# Power_Supplies.net
KiCad netlist of a schematic drawn in Altium Designer
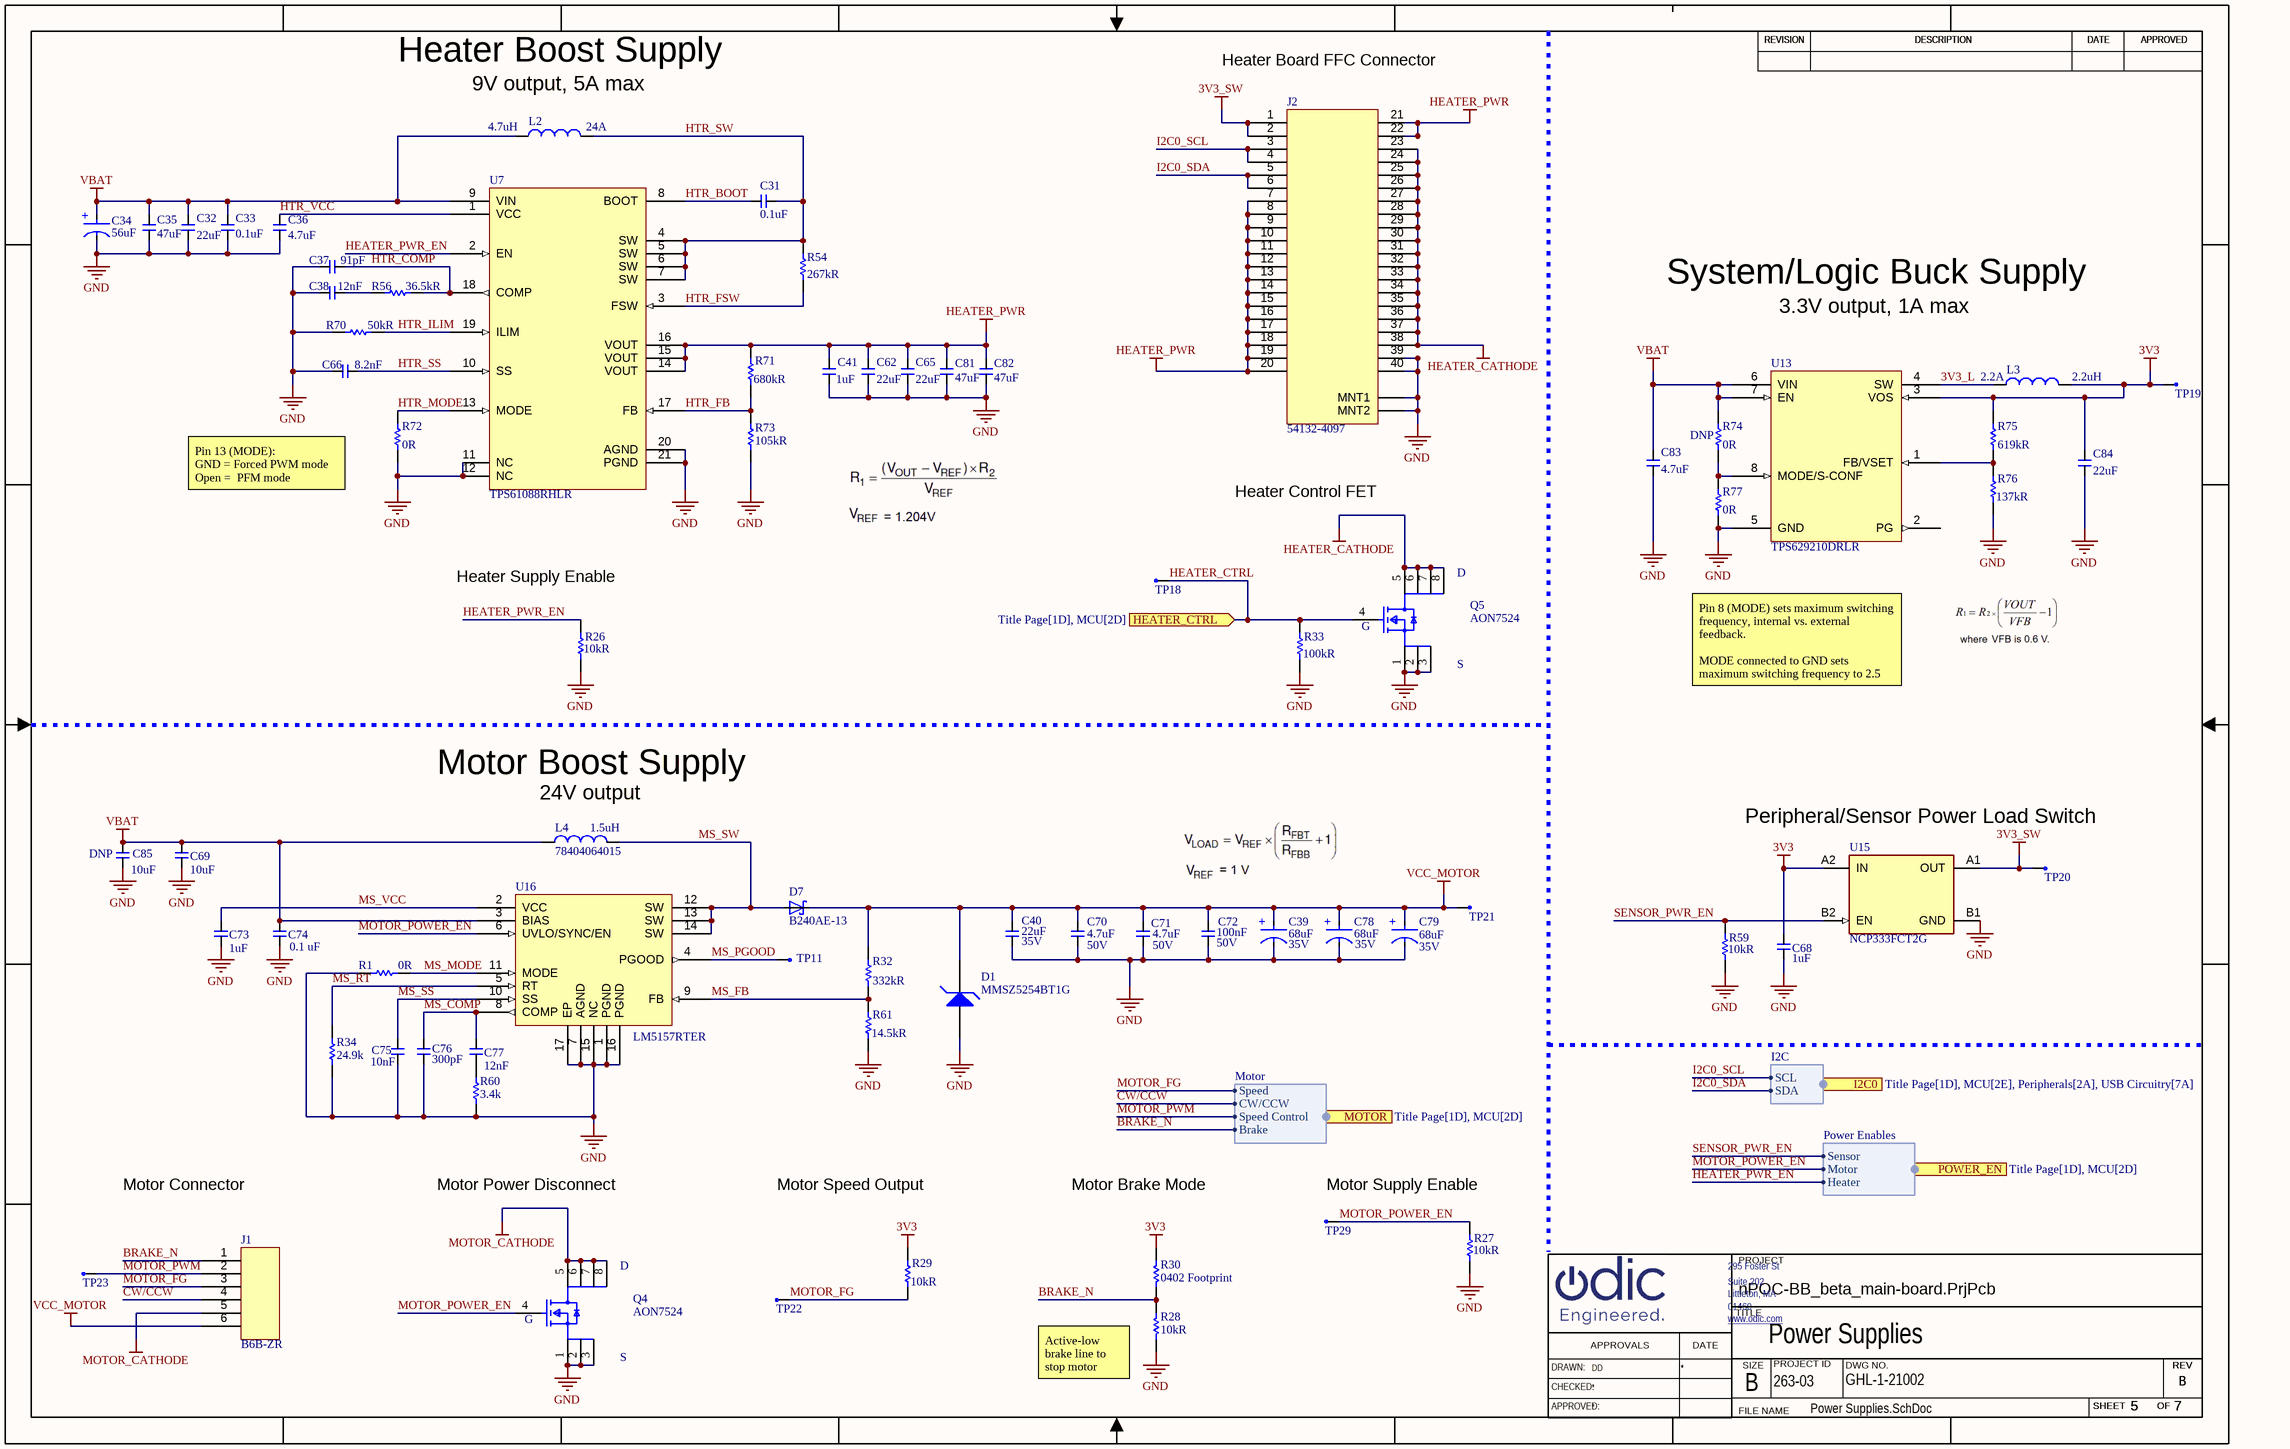
[diagram p0: Power Supplies.SchDoc]

(export (version "E")
  (design (tool "Eeschema 10.0.6"))
  (components
    (comp (ref "C31")
      (value "0.1uF")
      (footprint "C0402")
      (description "Ceramic capacitor SMD 0402 100nF 16V X7R 10%")
      (fields (field (name "VOLTAGE") "16V") (field (name "TOLERANCE") "10%"))
      (libsource (lib "Odic Inc") (part "cAP"))
    )
    (comp (ref "C32")
      (value "22uF")
      (footprint "C1206")
      (description "1206 22 uF 16 V ±10% Tolerance X5R SMT Multilayer Ceramic Capacitor")
      (fields (field (name "VOLTAGE") "16V") (field (name "TOLERANCE") "10%"))
      (libsource (lib "Odic Inc") (part "cAP"))
    )
    (comp (ref "C33")
      (value "0.1uF")
      (footprint "C0402")
      (description "Ceramic capacitor SMD 0402 100nF 16V X7R 10%")
      (fields (field (name "VOLTAGE") "16V") (field (name "TOLERANCE") "10%"))
      (libsource (lib "Odic Inc") (part "cAP"))
    )
    (comp (ref "C34")
      (value "56uF")
      (footprint "cap_panasonic_svpf_code-b6")
      (description "Cap Aluminum Polymer 56uF 20VDC 20%( 5 X 5.9mm) SMD 0.03 Ohm 2800mA 5000h 105C T/R")
      (fields (field (name "VOLTAGE") "20V") (field (name "TOLERANCE") "20%"))
      (libsource (lib "Odic Inc") (part "polcap"))
    )
    (comp (ref "C35")
      (value "47uF")
      (footprint "C1210")
      (description "Multilayer Ceramic Capacitor, 47 uF, 16 V, 10%, X5R, 1210 [3225 Metric]")
      (fields (field (name "TOLERANCE") "10%") (field (name "Comment") "C1210_47u_16V_10pct"))
      (libsource (lib "Odic Inc") (part "cAP"))
    )
    (comp (ref "C36")
      (value "4.7uF")
      (footprint "C0402")
      (description "Cap Ceramic 4.7uF 10V X5R 20% SMD 0402 85°C Paper T/R")
      (fields (field (name "TOLERANCE") "20%"))
      (libsource (lib "Odic Inc") (part "cAP"))
    )
    (comp (ref "C37")
      (value "91pF")
      (footprint "C0402")
      (description "Multilayer Ceramic Capacitors MLCC - SMD/SMT 50V 91pF C0G 0402 5%")
      (fields (field (name "TOLERANCE") "5%") (field (name "Comment") "C0402_91p_50V_5pct"))
      (libsource (lib "Odic Inc") (part "cAP"))
    )
    (comp (ref "C38")
      (value "12nF")
      (footprint "C0402")
      (description "0402 12 nF 16 V ±10% Tolerance X7R SMT Multilayer Ceramic Capacitor")
      (fields (field (name "VOLTAGE") "16V") (field (name "TOLERANCE") "10%"))
      (libsource (lib "Odic Inc") (part "cAP"))
    )
    (comp (ref "C39")
      (value "68uF")
      (footprint "C7361-38")
      (description "Cap Tant Solid 68uF 35V V CASE 20% (7.3 X 6.1 X 3.45mm) SMD 7361-38 0.5 Ohm 125AHA T/R")
      (fields
        (field (name "VOLTAGE RATING") "35V")
        (field (name "TOLERANCE") "20%")
        (field (name "Comment") "TAJV686M035RNJ")
      )
      (libsource (lib "Odic Inc") (part "polcap"))
    )
    (comp (ref "C40")
      (value "22uF")
      (footprint "c0805")
      (description "Multilayer Ceramic Capacitor, 22 uF, 35 V, ± 20%, X5R, 0805 [2012 Metric]")
      (fields
        (field (name "VOLTAGE RATING") "35V")
        (field (name "TOLERANCE") "20%")
        (field (name "Comment") "C0805_22u_35V_20pct")
      )
      (libsource (lib "Odic Inc") (part "cAP"))
    )
    (comp (ref "C41")
      (value "C0603_1u_25V_10pct")
      (footprint "C0603")
      (description "Multilayer Ceramic Capacitors (High dielectric type), 25V, 1 uF, ± 10 %, 0603, X5R/B, RoHS")
      (fields
        (field (name "CAPACITANCE") "1uF")
        (field (name "TOLERANCE") "10%")
        (field (name "VOLTAGE") "25V")
      )
      (libsource (lib "Odic Inc") (part "cAP"))
    )
    (comp (ref "C62")
      (value "22uF")
      (footprint "C1206")
      (description "1206 22 uF 16 V ±10% Tolerance X5R SMT Multilayer Ceramic Capacitor")
      (fields (field (name "VOLTAGE") "16V") (field (name "TOLERANCE") "10%"))
      (libsource (lib "Odic Inc") (part "cAP"))
    )
    (comp (ref "C65")
      (value "22uF")
      (footprint "C1206")
      (description "1206 22 uF 16 V ±10% Tolerance X5R SMT Multilayer Ceramic Capacitor")
      (fields (field (name "VOLTAGE") "16V") (field (name "TOLERANCE") "10%"))
      (libsource (lib "Odic Inc") (part "cAP"))
    )
    (comp (ref "C66")
      (value "8.2nF")
      (footprint "C0402")
      (description "0402 8.2 nF 16 V ±10% Tolerance X7R SMT Multilayer Ceramic Capacitor")
      (fields (field (name "TOLERANCE") "10%") (field (name "Comment") "C0402_8n2_16V_10pct"))
      (libsource (lib "Odic Inc") (part "cAP"))
    )
    (comp (ref "C68")
      (value "C0402_1u_6V3_10pct")
      (footprint "C0402")
      (description "Cap Ceramic 1uF 6.3V X5R 10% SMD 0402 85C Paper T/R")
      (fields (field (name "CAPACITANCE") "1uF") (field (name "TOLERANCE") "10%"))
      (libsource (lib "Odic Inc") (part "cAP"))
    )
    (comp (ref "C69")
      (value "10uF")
      (footprint "C0603")
      (description "Cap Ceramic 10uF 35V X5R 20% Pad SMD 0603 85C T/R")
      (fields (field (name "TOLERANCE") "20%"))
      (libsource (lib "Odic Inc") (part "cAP"))
    )
    (comp (ref "C70")
      (value "4.7uF")
      (footprint "c0805")
      (description "Multilayer Ceramic Capacitor, 4.7 uF, 35 V, ± 10%, X7S, 0805 [2012 Metric]")
      (fields (field (name "VOLTAGE RATING") "50V") (field (name "TOLERANCE") "10%"))
      (libsource (lib "Odic Inc") (part "cAP"))
    )
    (comp (ref "C71")
      (value "4.7uF")
      (footprint "c0805")
      (description "Multilayer Ceramic Capacitor, 4.7 uF, 35 V, ± 10%, X7S, 0805 [2012 Metric]")
      (fields (field (name "VOLTAGE RATING") "50V") (field (name "TOLERANCE") "10%"))
      (libsource (lib "Odic Inc") (part "cAP"))
    )
    (comp (ref "C72")
      (value "100nF")
      (footprint "C0603")
      (description "CAP CER 0.1UF 50V X7R 0603")
      (fields (field (name "VOLTAGE RATING") "50V") (field (name "TOLERANCE") "10%"))
      (libsource (lib "Odic Inc") (part "cAP"))
    )
    (comp (ref "C73")
      (value "1uF")
      (footprint "C0603")
      (description "CAP CER 1UF 16V X5R 0603")
      (fields (field (name "TOLERANCE") "10%") (field (name "VOLTAGE") "16V"))
      (libsource (lib "Odic Inc") (part "cAP"))
    )
    (comp (ref "C74")
      (value "C0805_0u1_25V_10pct")
      (footprint "c0805")
      (description "Cap Cer 0.1UF 25V X7R 0805")
      (fields (field (name "CAPACITANCE") "0.1 uF") (field (name "TOLERANCE") "10%"))
      (libsource (lib "Odic Inc") (part "cAP"))
    )
    (comp (ref "C75")
      (value "10nF")
      (footprint "C0402")
      (description "Multilayer Ceramic Capacitor, 0.01 uF, 35 V, ± 10%, X7R, 0402 [1005 Metric]")
      (fields (field (name "TOLERANCE") "10%") (field (name "Comment") "C0402_10n_35V_10pct"))
      (libsource (lib "Odic Inc") (part "cAP"))
    )
    (comp (ref "C76")
      (value "300pF")
      (footprint "C0402")
      (description "Cap Ceramic 300pF 50V C0G 5% SMD 0402 125°C Paper T/R")
      (fields (field (name "TOLERANCE") "5%") (field (name "Comment") "C0402_300p_50V_5pct"))
      (libsource (lib "Odic Inc") (part "cAP"))
    )
    (comp (ref "C77")
      (value "12nF")
      (footprint "C0402")
      (description "0402 12 nF 16 V ±10% Tolerance X7R SMT Multilayer Ceramic Capacitor")
      (fields (field (name "VOLTAGE") "16V") (field (name "TOLERANCE") "10%"))
      (libsource (lib "Odic Inc") (part "cAP"))
    )
    (comp (ref "C78")
      (value "68uF")
      (footprint "C7361-38")
      (description "Cap Tant Solid 68uF 35V V CASE 20% (7.3 X 6.1 X 3.45mm) SMD 7361-38 0.5 Ohm 125AHA T/R")
      (fields
        (field (name "VOLTAGE RATING") "35V")
        (field (name "TOLERANCE") "20%")
        (field (name "Comment") "TAJV686M035RNJ")
      )
      (libsource (lib "Odic Inc") (part "polcap"))
    )
    (comp (ref "C79")
      (value "68uF")
      (footprint "C7361-38")
      (description "Cap Tant Solid 68uF 35V V CASE 20% (7.3 X 6.1 X 3.45mm) SMD 7361-38 0.5 Ohm 125AHA T/R")
      (fields
        (field (name "VOLTAGE RATING") "35V")
        (field (name "TOLERANCE") "20%")
        (field (name "Comment") "TAJV686M035RNJ")
      )
      (libsource (lib "Odic Inc") (part "polcap"))
    )
    (comp (ref "C81")
      (value "47uF")
      (footprint "C1210")
      (description "Multilayer Ceramic Capacitor, 47 uF, 16 V, 10%, X5R, 1210 [3225 Metric]")
      (fields (field (name "TOLERANCE") "10%") (field (name "Comment") "C1210_47u_16V_10pct"))
      (libsource (lib "Odic Inc") (part "cAP"))
    )
    (comp (ref "C82")
      (value "47uF")
      (footprint "C1210")
      (description "Multilayer Ceramic Capacitor, 47 uF, 16 V, 10%, X5R, 1210 [3225 Metric]")
      (fields (field (name "TOLERANCE") "10%") (field (name "Comment") "C1210_47u_16V_10pct"))
      (libsource (lib "Odic Inc") (part "cAP"))
    )
    (comp (ref "C83")
      (value "4.7uF")
      (footprint "c0805")
      (description "Multilayer Ceramic Capacitor, 4.7 uF, 16 V, ± 10%, X5R, 0805 [2012 Metric]")
      (fields (field (name "VOLTAGE") "16V") (field (name "TOLERANCE") "10%"))
      (libsource (lib "Odic Inc") (part "cAP"))
    )
    (comp (ref "C84")
      (value "C0603_22u_6V3_20pct")
      (footprint "C0603")
      (description "CAP CER 22UF 6.3V X5R 0603")
      (fields
        (field (name "CAPACITANCE") "22uF")
        (field (name "TOLERANCE") "20%")
        (field (name "VOLTAGE") "6.3V")
      )
      (libsource (lib "Odic Inc") (part "cAP"))
    )
    (comp (ref "C85")
      (value "10uF")
      (footprint "C0603")
      (description "Cap Ceramic 10uF 35V X5R 20% Pad SMD 0603 85C T/R")
      (fields (field (name "INSTALL") "DNP") (field (name "TOLERANCE") "20%"))
      (libsource (lib "Odic Inc") (part "cAP"))
    )
    (comp (ref "D1")
      (value "MMSZ5254BT1G")
      (footprint "sod123")
      (description "MMSZ5254BT1G Zener Diode, 27V 5% 500 mW SMT 2-Pin SOD-123")
      (fields (field (name "TOLERANCE") "5%"))
      (libsource (lib "Odic Inc") (part "Zener Symbol"))
    )
    (comp (ref "D7")
      (value "B240AE-13")
      (footprint "sma")
      (description "Diode Schottky 40V 2A 2-Pin DO-214AC T/R")
      (libsource (lib "Odic Inc") (part "B240AE-13"))
    )
    (comp (ref "J1")
      (value "B6B-ZR")
      (footprint "jst-b6b-zr")
      (description "Header B6B-ZR, 1.50mm, 6-contacts, top entry, THT, /2000/box")
      (libsource (lib "Odic Inc") (part "B6B-ZR-Symbol-1"))
    )
    (comp (ref "J2")
      (value "54132-4097")
      (footprint "molex_54132-4097")
      (description ".50MM Ffc/fpc Connectors 40CKT R/a SMT Zif Botton Contact")
      (libsource (lib "Odic Inc") (part "54132-4097-Symbol-1"))
    )
    (comp (ref "L2")
      (value "4.7uH")
      (footprint "ind2_vishay_ihlp5050ce")
      (description "Inductor Power Shielded Wirewound 4.7uH 20% 100KHz Powdered Iron 10A 15mOhm DCR 5050 T/R")
      (fields
        (field (name "SATURATION CURRENT") "24A")
        (field (name "TOLERANCE") "20%")
        (field (name "Comment") "IHLP5050CEER4R7M01")
      )
      (libsource (lib "Odic Inc") (part "IND"))
    )
    (comp (ref "L3")
      (value "DFE252012PD-2R2M=P2")
      (footprint "ind2_2520")
      (description "Ind Power Chip Shielded Wirewound 2.2uH 20% 1MHz Metal 2.2A 1008 Emboss T/R")
      (fields
        (field (name "INDUCTANCE") "2.2uH")
        (field (name "CURRENT RATING") "2.2A")
        (field (name "TOLERANCE") "+/-20%")
      )
      (libsource (lib "Odic Inc") (part "IND"))
    )
    (comp (ref "L4")
      (value "78404064015")
      (footprint "ind2_wurth_78404064015")
      (description "WE-LQSA SMT Semi-Shielded Power Inductor 1.5uH 6.1 A 13mOhm Max")
      (fields (field (name "ALTIUM_VALUE") "1.5uH"))
      (libsource (lib "Odic Inc") (part "IND"))
    )
    (comp (ref "Q4")
      (value "AON7524")
      (footprint "dfn8_3x3_p65mm_fet")
      (description "Trans Mosfet N-ch 30V 28A 8-PIN Dfn-a Ep")
      (libsource (lib "Odic Inc") (part "e0baf4780622716b99a4fe4ad34e686"))
    )
    (comp (ref "Q5")
      (value "AON7524")
      (footprint "dfn8_3x3_p65mm_fet")
      (description "Trans Mosfet N-ch 30V 28A 8-PIN Dfn-a Ep")
      (libsource (lib "Odic Inc") (part "e0baf4780622716b99a4fe4ad34e686"))
    )
    (comp (ref "R1")
      (value "0R")
      (footprint "R0402")
      (description "RES 0 OHM JUMPER 1/16W 0402")
      (libsource (lib "Odic Inc") (part "RES"))
    )
    (comp (ref "R26")
      (value "R0402_10k_1pct")
      (footprint "R0402")
      (description "Res Thick Film 0402 10K Ohm 1% 1/16W ±100ppm/°C Molded SMD SMD T/R")
      (fields (field (name "RESISTANCE") "10kR") (field (name "TOLERANCE") "1%"))
      (libsource (lib "Odic Inc") (part "RES"))
    )
    (comp (ref "R27")
      (value "R0402_10k_1pct")
      (footprint "R0402")
      (description "Res Thick Film 0402 10K Ohm 1% 1/16W ±100ppm/°C Molded SMD SMD T/R")
      (fields (field (name "RESISTANCE") "10kR") (field (name "TOLERANCE") "1%"))
      (libsource (lib "Odic Inc") (part "RES"))
    )
    (comp (ref "R28")
      (value "R0402_10k_1pct")
      (footprint "R0402")
      (description "Res Thick Film 0402 10K Ohm 1% 1/16W ±100ppm/°C Molded SMD SMD T/R")
      (fields (field (name "RESISTANCE") "10kR") (field (name "TOLERANCE") "1%"))
      (libsource (lib "Odic Inc") (part "RES"))
    )
    (comp (ref "R29")
      (value "R0402_10k_1pct")
      (footprint "R0402")
      (description "Res Thick Film 0402 10K Ohm 1% 1/16W ±100ppm/°C Molded SMD SMD T/R")
      (fields (field (name "RESISTANCE") "10kR") (field (name "TOLERANCE") "1%"))
      (libsource (lib "Odic Inc") (part "RES"))
    )
    (comp (ref "R30")
      (value "0402 Footprint")
      (footprint "R0402")
      (description "Unpopulated 0402 pads. No part number associated with this \"component\"")
      (libsource (lib "Odic Inc") (part "RES"))
    )
    (comp (ref "R32")
      (value "332kR")
      (footprint "R0402")
      (description "Res Thick Film 0402 332K Ohm 1% 0.1W(1/10W) ±100ppm/°C Pad SMD Automotive T/R")
      (fields (field (name "TOLERANCE") "1%") (field (name "Comment") "R0402_332k_1pct"))
      (libsource (lib "Odic Inc") (part "RES"))
    )
    (comp (ref "R33")
      (value "R0402_100k_1pct")
      (footprint "R0402")
      (description "Res General Purpose Thick Film 0402 100K Ohm 1% 1/16W ±100ppm/°C Molded SMD Paper T/R")
      (fields (field (name "RESISTANCE") "100kR") (field (name "TOLERANCE") "1%"))
      (libsource (lib "Odic Inc") (part "RES"))
    )
    (comp (ref "R34")
      (value "24.9k")
      (footprint "R0402")
      (description "Res Thick Film 0402 24.9K Ohm 1% 1/10W ±100ppm/¦C SMD Punched Carrier T/R")
      (fields (field (name "TOLERANCE") "1%"))
      (libsource (lib "Odic Inc") (part "RES"))
    )
    (comp (ref "R54")
      (value "267kR")
      (footprint "R0402")
      (description "Res Thick Film 0402 267K Ohm 1% 0.063W ±100ppm/°C Molded SMD Paper T/R")
      (fields (field (name "TOLERANCE") "1%") (field (name "Comment") "R0402_267k_1pct"))
      (libsource (lib "Odic Inc") (part "RES"))
    )
    (comp (ref "R56")
      (value "36.5kR")
      (footprint "R0402")
      (description "SMD Chip Resistor, 36.5 kOhm, ï¿½ 1%, 63 mW, 0402 [1005 Metric], Thick Film, General Purpose")
      (fields (field (name "TOLERANCE") "1%") (field (name "Comment") "R0402_36k5_1pct"))
      (libsource (lib "Odic Inc") (part "RES"))
    )
    (comp (ref "R59")
      (value "R0402_10k_1pct")
      (footprint "R0402")
      (description "Res Thick Film 0402 10K Ohm 1% 1/16W ±100ppm/°C Molded SMD SMD T/R")
      (fields (field (name "RESISTANCE") "10kR") (field (name "TOLERANCE") "1%"))
      (libsource (lib "Odic Inc") (part "RES"))
    )
    (comp (ref "R60")
      (value "3.4k")
      (footprint "R0402")
      (description "SMD Chip Resistor, 3.4 kOhm, ± 1%, 100 mW, 0402 [1005 Metric], Thick Film, Precision")
      (fields (field (name "TOLERANCE") "1%"))
      (libsource (lib "Odic Inc") (part "RES"))
    )
    (comp (ref "R61")
      (value "14.5kR")
      (footprint "R0402")
      (description "RN73H 0402 (1005Metric) Chip Resistor ±1% ±25ppm/C 14.5kOhm 0.063W 1/16W")
      (fields (field (name "TOLERANCE") "1%") (field (name "Comment") "R0402_14k5_1pct"))
      (libsource (lib "Odic Inc") (part "RES"))
    )
    (comp (ref "R70")
      (value "50kR")
      (footprint "R0402")
      (fields (field (name "TOLERANCE") "1%") (field (name "Comment") "R0402_50k_1pct"))
      (libsource (lib "Odic Inc") (part "RES"))
    )
    (comp (ref "R71")
      (value "680kR")
      (footprint "R0402")
      (description "Res Thick Film 0402 680K Ohm 1% 1/16W ±100ppm/°C Molded SMD SMD Paper T/R")
      (fields (field (name "TOLERANCE") "1%") (field (name "Comment") "R0402_680k_1pct"))
      (libsource (lib "Odic Inc") (part "RES"))
    )
    (comp (ref "R72")
      (value "R0402_0R")
      (footprint "R0402")
      (description "RES 0 OHM JUMPER 1/16W 0402")
      (fields (field (name "RESISTANCE") "0R"))
      (libsource (lib "Odic Inc") (part "RES"))
    )
    (comp (ref "R73")
      (value "105kR")
      (footprint "R0402")
      (description "SMD Chip Resistor, 105 kOhm, ± 1%, 63 mW, 0402 [1005 Metric], Thick Film, General Purpose")
      (fields (field (name "TOLERANCE") "1%") (field (name "Comment") "R0402_105k_1pct"))
      (libsource (lib "Odic Inc") (part "RES"))
    )
    (comp (ref "R74")
      (value "R0402_0R")
      (footprint "R0402")
      (description "RES 0 OHM JUMPER 1/16W 0402")
      (fields (field (name "INSTALL") "DNP") (field (name "RESISTANCE") "0R"))
      (libsource (lib "Odic Inc") (part "RES"))
    )
    (comp (ref "R75")
      (value "619kR")
      (footprint "R0402")
      (description "RC FIXED RESISTOR 0402 (1005Metric) Chip Resistor ±1% ±100ppm/C 619kOhm 0.063W 1/16W")
      (fields (field (name "TOLERANCE") "1%") (field (name "Comment") "R0402_619k_1pct"))
      (libsource (lib "Odic Inc") (part "RES"))
    )
    (comp (ref "R76")
      (value "137kR")
      (footprint "R0402")
      (description "SMD Chip Resistor, 137 kOhm, ± 1%, 63 mW, 0402 [1005 Metric], Thick Film, General Purpose")
      (fields (field (name "TOLERANCE") "1%") (field (name "Comment") "R0402_137k_1pct"))
      (libsource (lib "Odic Inc") (part "RES"))
    )
    (comp (ref "R77")
      (value "R0402_0R")
      (footprint "R0402")
      (description "RES 0 OHM JUMPER 1/16W 0402")
      (fields (field (name "RESISTANCE") "0R"))
      (libsource (lib "Odic Inc") (part "RES"))
    )
    (comp (ref "TP11")
      (value "TPC30")
      (footprint "tpc30")
      (description "Test Point Circle 30")
      (libsource (lib "Odic Inc") (part "TPC"))
    )
    (comp (ref "TP18")
      (value "TPC30")
      (footprint "tpc30")
      (description "Test Point Circle 30")
      (libsource (lib "Odic Inc") (part "TPC"))
    )
    (comp (ref "TP19")
      (value "TPC30")
      (footprint "tpc30")
      (description "Test Point Circle 30")
      (libsource (lib "Odic Inc") (part "TPC"))
    )
    (comp (ref "TP20")
      (value "TPC30")
      (footprint "tpc30")
      (description "Test Point Circle 30")
      (libsource (lib "Odic Inc") (part "TPC"))
    )
    (comp (ref "TP21")
      (value "TPC30")
      (footprint "tpc30")
      (description "Test Point Circle 30")
      (libsource (lib "Odic Inc") (part "TPC"))
    )
    (comp (ref "TP22")
      (value "TPC30")
      (footprint "tpc30")
      (description "Test Point Circle 30")
      (libsource (lib "Odic Inc") (part "TPC"))
    )
    (comp (ref "TP23")
      (value "TPC30")
      (footprint "tpc30")
      (description "Test Point Circle 30")
      (libsource (lib "Odic Inc") (part "TPC"))
    )
    (comp (ref "TP29")
      (value "TPC30")
      (footprint "tpc30")
      (description "Test Point Circle 30")
      (libsource (lib "Odic Inc") (part "TPC"))
    )
    (comp (ref "U7")
      (value "TPS61088RHLR")
      (footprint "qfn20_3p5x4p5_p5mm")
      (description "IC REG BOOST ADJ 10A SYNC 20VQFN")
      (libsource (lib "Odic Inc") (part "TPS61088RHLR-Symbol-1"))
    )
    (comp (ref "U13")
      (value "TPS629210DRLR")
      (footprint "SOT-583")
      (libsource (lib "Odic Inc") (part "TPS629210DRLR-Symbol-1"))
    )
    (comp (ref "U15")
      (value "NCP333FCT2G")
      (footprint "bga4_p743xp743_p4mm")
      (description "IC LOAD SWITCH W/DIS 1.5A 4WLCSP")
      (libsource (lib "Odic Inc") (part "97019fd276bc7644be76e1f711e9589"))
    )
    (comp (ref "U16")
      (value "LM5157RTER")
      (footprint "qfn16_3x3_p5mm_thpad")
      (libsource (lib "Odic Inc") (part "LM5157RTER-Symbol-1"))
    )
  )
  (nets
    (net (code "5") (name "/3V3_L") (class "Default")
      (node (ref "L3") (pin "1") (pinfunction "1_1") (pintype "passive"))
      (node (ref "U13") (pin "4") (pinfunction "SW_4") (pintype "passive"))
    )
    (net (code "6") (name "/BRAKE_N") (class "Default")
      (node (ref "J1") (pin "1") (pinfunction "1_1") (pintype "passive"))
      (node (ref "R28") (pin "1") (pinfunction "1_1") (pintype "passive"))
      (node (ref "R30") (pin "2") (pinfunction "2_2") (pintype "passive"))
    )
    (net (code "7") (name "/CW{slash}CCW") (class "Default")
      (node (ref "J1") (pin "4") (pinfunction "4_4") (pintype "passive"))
    )
    (net (code "8") (name "/HEATER_CTRL") (class "Default")
      (node (ref "Q5") (pin "4") (pinfunction "G_4") (pintype "passive"))
      (node (ref "R33") (pin "2") (pinfunction "2_2") (pintype "passive"))
      (node (ref "TP18") (pin "1") (pinfunction "1_1") (pintype "passive"))
    )
    (net (code "9") (name "/HEATER_PWR_EN") (class "Default")
      (node (ref "R26") (pin "1") (pinfunction "1_1") (pintype "passive"))
      (node (ref "U7") (pin "2") (pinfunction "EN_2") (pintype "input"))
    )
    (net (code "10") (name "/HTR_BOOT") (class "Default")
      (node (ref "C31") (pin "2") (pinfunction "2_2") (pintype "passive"))
      (node (ref "U7") (pin "8") (pinfunction "BOOT_8") (pintype "passive"))
    )
    (net (code "11") (name "/HTR_COMP") (class "Default")
      (node (ref "C37") (pin "2") (pinfunction "2_2") (pintype "passive"))
      (node (ref "R56") (pin "2") (pinfunction "2_2") (pintype "passive"))
      (node (ref "U7") (pin "18") (pinfunction "COMP_18") (pintype "output"))
    )
    (net (code "12") (name "/HTR_FB") (class "Default")
      (node (ref "R71") (pin "1") (pinfunction "1_1") (pintype "passive"))
      (node (ref "R73") (pin "2") (pinfunction "2_2") (pintype "passive"))
      (node (ref "U7") (pin "17") (pinfunction "FB_17") (pintype "input"))
    )
    (net (code "13") (name "/HTR_FSW") (class "Default")
      (node (ref "R54") (pin "1") (pinfunction "1_1") (pintype "passive"))
      (node (ref "U7") (pin "3") (pinfunction "FSW_3") (pintype "input"))
    )
    (net (code "14") (name "/HTR_ILIM") (class "Default")
      (node (ref "R70") (pin "2") (pinfunction "2_2") (pintype "passive"))
      (node (ref "U7") (pin "19") (pinfunction "ILIM_19") (pintype "input"))
    )
    (net (code "15") (name "/HTR_MODE") (class "Default")
      (node (ref "R72") (pin "2") (pinfunction "2_2") (pintype "passive"))
      (node (ref "U7") (pin "13") (pinfunction "MODE_13") (pintype "input"))
    )
    (net (code "16") (name "/HTR_SS") (class "Default")
      (node (ref "C66") (pin "2") (pinfunction "2_2") (pintype "passive"))
      (node (ref "U7") (pin "10") (pinfunction "SS_10") (pintype "input"))
    )
    (net (code "17") (name "/HTR_SW") (class "Default")
      (node (ref "C31") (pin "1") (pinfunction "1_1") (pintype "passive"))
      (node (ref "L2") (pin "2") (pinfunction "2_2") (pintype "passive"))
      (node (ref "R54") (pin "2") (pinfunction "2_2") (pintype "passive"))
      (node (ref "U7") (pin "4") (pinfunction "SW_4") (pintype "passive"))
      (node (ref "U7") (pin "5") (pinfunction "SW_5") (pintype "passive"))
      (node (ref "U7") (pin "6") (pinfunction "SW_6") (pintype "passive"))
      (node (ref "U7") (pin "7") (pinfunction "SW_7") (pintype "passive"))
    )
    (net (code "18") (name "/HTR_VCC") (class "Default")
      (node (ref "C36") (pin "2") (pinfunction "2_2") (pintype "passive"))
      (node (ref "U7") (pin "1") (pinfunction "VCC_1") (pintype "passive"))
    )
    (net (code "19") (name "/I2C0_SCL") (class "Default")
      (node (ref "J2") (pin "3") (pinfunction "3_3") (pintype "passive"))
      (node (ref "J2") (pin "4") (pinfunction "4_4") (pintype "passive"))
    )
    (net (code "20") (name "/I2C0_SDA") (class "Default")
      (node (ref "J2") (pin "5") (pinfunction "5_5") (pintype "passive"))
      (node (ref "J2") (pin "6") (pinfunction "6_6") (pintype "passive"))
    )
    (net (code "21") (name "/MOTOR_FG") (class "Default")
      (node (ref "J1") (pin "3") (pinfunction "3_3") (pintype "passive"))
      (node (ref "R29") (pin "1") (pinfunction "1_1") (pintype "passive"))
      (node (ref "TP22") (pin "1") (pinfunction "1_1") (pintype "passive"))
    )
    (net (code "22") (name "/MOTOR_POWER_EN") (class "Default")
      (node (ref "Q4") (pin "4") (pinfunction "G_4") (pintype "passive"))
      (node (ref "R27") (pin "1") (pinfunction "1_1") (pintype "passive"))
      (node (ref "TP29") (pin "1") (pinfunction "1_1") (pintype "passive"))
      (node (ref "U16") (pin "6") (pinfunction "UVLO/SYNC/EN_6") (pintype "input"))
    )
    (net (code "23") (name "/MOTOR_PWM") (class "Default")
      (node (ref "J1") (pin "2") (pinfunction "2_2") (pintype "passive"))
      (node (ref "TP23") (pin "1") (pinfunction "1_1") (pintype "passive"))
    )
    (net (code "24") (name "/MS_COMP") (class "Default")
      (node (ref "C76") (pin "2") (pinfunction "2_2") (pintype "passive"))
      (node (ref "C77") (pin "2") (pinfunction "2_2") (pintype "passive"))
      (node (ref "U16") (pin "8") (pinfunction "COMP_8") (pintype "output"))
    )
    (net (code "25") (name "/MS_FB") (class "Default")
      (node (ref "R32") (pin "1") (pinfunction "1_1") (pintype "passive"))
      (node (ref "R61") (pin "2") (pinfunction "2_2") (pintype "passive"))
      (node (ref "U16") (pin "9") (pinfunction "FB_9") (pintype "input"))
    )
    (net (code "26") (name "/MS_MODE") (class "Default")
      (node (ref "R1") (pin "2") (pinfunction "2_2") (pintype "passive"))
      (node (ref "U16") (pin "11") (pinfunction "MODE_11") (pintype "input"))
    )
    (net (code "27") (name "/MS_PGOOD") (class "Default")
      (node (ref "TP11") (pin "1") (pinfunction "1_1") (pintype "passive"))
      (node (ref "U16") (pin "4") (pinfunction "PGOOD_4") (pintype "output"))
    )
    (net (code "28") (name "/MS_RT") (class "Default")
      (node (ref "R34") (pin "2") (pinfunction "2_2") (pintype "passive"))
      (node (ref "U16") (pin "5") (pinfunction "RT_5") (pintype "input"))
    )
    (net (code "29") (name "/MS_SS") (class "Default")
      (node (ref "C75") (pin "2") (pinfunction "2_2") (pintype "passive"))
      (node (ref "U16") (pin "10") (pinfunction "SS_10") (pintype "input"))
    )
    (net (code "30") (name "/MS_SW") (class "Default")
      (node (ref "D7") (pin "A") (pinfunction "A_A") (pintype "passive"))
      (node (ref "L4") (pin "2") (pinfunction "2_2") (pintype "passive"))
      (node (ref "U16") (pin "12") (pinfunction "SW_12") (pintype "passive"))
      (node (ref "U16") (pin "13") (pinfunction "SW_13") (pintype "passive"))
      (node (ref "U16") (pin "14") (pinfunction "SW_14") (pintype "passive"))
    )
    (net (code "31") (name "/MS_VCC") (class "Default")
      (node (ref "C73") (pin "2") (pinfunction "2_2") (pintype "passive"))
      (node (ref "U16") (pin "2") (pinfunction "VCC_2") (pintype "power_in"))
    )
    (net (code "32") (name "/SENSOR_PWR_EN") (class "Default")
      (node (ref "R59") (pin "1") (pinfunction "1_1") (pintype "passive"))
      (node (ref "U15") (pin "B2") (pinfunction "EN_B2") (pintype "input"))
    )
    (net (code "36") (name "3V3") (class "Default")
      (node (ref "C68") (pin "2") (pinfunction "2_2") (pintype "passive"))
      (node (ref "C84") (pin "2") (pinfunction "2_2") (pintype "passive"))
      (node (ref "L3") (pin "2") (pinfunction "2_2") (pintype "passive"))
      (node (ref "R29") (pin "2") (pinfunction "2_2") (pintype "passive"))
      (node (ref "R30") (pin "1") (pinfunction "1_1") (pintype "passive"))
      (node (ref "R75") (pin "2") (pinfunction "2_2") (pintype "passive"))
      (node (ref "TP19") (pin "1") (pinfunction "1_1") (pintype "passive"))
      (node (ref "U13") (pin "3") (pinfunction "VOS_3") (pintype "input"))
      (node (ref "U15") (pin "A2") (pinfunction "IN_A2") (pintype "power_in"))
    )
    (net (code "37") (name "3V3_SW") (class "Default")
      (node (ref "J2") (pin "1") (pinfunction "1_1") (pintype "passive"))
      (node (ref "J2") (pin "2") (pinfunction "2_2") (pintype "passive"))
      (node (ref "TP20") (pin "1") (pinfunction "1_1") (pintype "passive"))
      (node (ref "U15") (pin "A1") (pinfunction "OUT_A1") (pintype "power_in"))
    )
    (net (code "38") (name "GND") (class "Default")
      (node (ref "C32") (pin "1") (pinfunction "1_1") (pintype "passive"))
      (node (ref "C33") (pin "2") (pinfunction "2_2") (pintype "passive"))
      (node (ref "C34") (pin "2") (pinfunction "2_2") (pintype "passive"))
      (node (ref "C35") (pin "1") (pinfunction "1_1") (pintype "passive"))
      (node (ref "C36") (pin "1") (pinfunction "1_1") (pintype "passive"))
      (node (ref "C37") (pin "1") (pinfunction "1_1") (pintype "passive"))
      (node (ref "C38") (pin "1") (pinfunction "1_1") (pintype "passive"))
      (node (ref "C39") (pin "2") (pinfunction "2_2") (pintype "passive"))
      (node (ref "C40") (pin "1") (pinfunction "1_1") (pintype "passive"))
      (node (ref "C41") (pin "1") (pinfunction "1_1") (pintype "passive"))
      (node (ref "C62") (pin "1") (pinfunction "1_1") (pintype "passive"))
      (node (ref "C65") (pin "1") (pinfunction "1_1") (pintype "passive"))
      (node (ref "C66") (pin "1") (pinfunction "1_1") (pintype "passive"))
      (node (ref "C68") (pin "1") (pinfunction "1_1") (pintype "passive"))
      (node (ref "C69") (pin "1") (pinfunction "1_1") (pintype "passive"))
      (node (ref "C70") (pin "1") (pinfunction "1_1") (pintype "passive"))
      (node (ref "C71") (pin "1") (pinfunction "1_1") (pintype "passive"))
      (node (ref "C72") (pin "1") (pinfunction "1_1") (pintype "passive"))
      (node (ref "C73") (pin "1") (pinfunction "1_1") (pintype "passive"))
      (node (ref "C74") (pin "1") (pinfunction "1_1") (pintype "passive"))
      (node (ref "C75") (pin "1") (pinfunction "1_1") (pintype "passive"))
      (node (ref "C76") (pin "1") (pinfunction "1_1") (pintype "passive"))
      (node (ref "C78") (pin "2") (pinfunction "2_2") (pintype "passive"))
      (node (ref "C79") (pin "2") (pinfunction "2_2") (pintype "passive"))
      (node (ref "C81") (pin "1") (pinfunction "1_1") (pintype "passive"))
      (node (ref "C82") (pin "1") (pinfunction "1_1") (pintype "passive"))
      (node (ref "C83") (pin "1") (pinfunction "1_1") (pintype "passive"))
      (node (ref "C84") (pin "1") (pinfunction "1_1") (pintype "passive"))
      (node (ref "C85") (pin "1") (pinfunction "1_1") (pintype "passive"))
      (node (ref "D1") (pin "A") (pinfunction "A_A") (pintype "passive"))
      (node (ref "J2") (pin "39") (pinfunction "39_39") (pintype "passive"))
      (node (ref "J2") (pin "40") (pinfunction "40_40") (pintype "passive"))
      (node (ref "J2") (pin "MNT1") (pinfunction "MNT1_MNT1") (pintype "passive"))
      (node (ref "J2") (pin "MNT2") (pinfunction "MNT2_MNT2") (pintype "passive"))
      (node (ref "Q4") (pin "1") (pinfunction "S_1") (pintype "passive"))
      (node (ref "Q4") (pin "2") (pinfunction "S_2") (pintype "passive"))
      (node (ref "Q4") (pin "3") (pinfunction "S_3") (pintype "passive"))
      (node (ref "Q5") (pin "1") (pinfunction "S_1") (pintype "passive"))
      (node (ref "Q5") (pin "2") (pinfunction "S_2") (pintype "passive"))
      (node (ref "Q5") (pin "3") (pinfunction "S_3") (pintype "passive"))
      (node (ref "R1") (pin "1") (pinfunction "1_1") (pintype "passive"))
      (node (ref "R26") (pin "2") (pinfunction "2_2") (pintype "passive"))
      (node (ref "R27") (pin "2") (pinfunction "2_2") (pintype "passive"))
      (node (ref "R28") (pin "2") (pinfunction "2_2") (pintype "passive"))
      (node (ref "R33") (pin "1") (pinfunction "1_1") (pintype "passive"))
      (node (ref "R34") (pin "1") (pinfunction "1_1") (pintype "passive"))
      (node (ref "R59") (pin "2") (pinfunction "2_2") (pintype "passive"))
      (node (ref "R60") (pin "1") (pinfunction "1_1") (pintype "passive"))
      (node (ref "R61") (pin "1") (pinfunction "1_1") (pintype "passive"))
      (node (ref "R70") (pin "1") (pinfunction "1_1") (pintype "passive"))
      (node (ref "R72") (pin "1") (pinfunction "1_1") (pintype "passive"))
      (node (ref "R73") (pin "1") (pinfunction "1_1") (pintype "passive"))
      (node (ref "R76") (pin "1") (pinfunction "1_1") (pintype "passive"))
      (node (ref "R77") (pin "1") (pinfunction "1_1") (pintype "passive"))
      (node (ref "U13") (pin "5") (pinfunction "GND_5") (pintype "passive"))
      (node (ref "U15") (pin "B1") (pinfunction "GND_B1") (pintype "power_in"))
      (node (ref "U16") (pin "1") (pinfunction "PGND_1") (pintype "passive"))
      (node (ref "U16") (pin "15") (pinfunction "NC_15") (pintype "passive"))
      (node (ref "U16") (pin "16") (pinfunction "PGND_16") (pintype "passive"))
      (node (ref "U16") (pin "17") (pinfunction "EP_17") (pintype "passive"))
      (node (ref "U16") (pin "7") (pinfunction "AGND_7") (pintype "passive"))
      (node (ref "U7") (pin "11") (pinfunction "NC_11") (pintype "passive"))
      (node (ref "U7") (pin "12") (pinfunction "NC_12") (pintype "passive"))
      (node (ref "U7") (pin "20") (pinfunction "AGND_20") (pintype "passive"))
      (node (ref "U7") (pin "21") (pinfunction "PGND_21") (pintype "passive"))
    )
    (net (code "39") (name "HEATER_CATHODE") (class "Default")
      (node (ref "J2") (pin "23") (pinfunction "23_23") (pintype "passive"))
      (node (ref "J2") (pin "24") (pinfunction "24_24") (pintype "passive"))
      (node (ref "J2") (pin "25") (pinfunction "25_25") (pintype "passive"))
      (node (ref "J2") (pin "26") (pinfunction "26_26") (pintype "passive"))
      (node (ref "J2") (pin "27") (pinfunction "27_27") (pintype "passive"))
      (node (ref "J2") (pin "28") (pinfunction "28_28") (pintype "passive"))
      (node (ref "J2") (pin "29") (pinfunction "29_29") (pintype "passive"))
      (node (ref "J2") (pin "30") (pinfunction "30_30") (pintype "passive"))
      (node (ref "J2") (pin "31") (pinfunction "31_31") (pintype "passive"))
      (node (ref "J2") (pin "32") (pinfunction "32_32") (pintype "passive"))
      (node (ref "J2") (pin "33") (pinfunction "33_33") (pintype "passive"))
      (node (ref "J2") (pin "34") (pinfunction "34_34") (pintype "passive"))
      (node (ref "J2") (pin "35") (pinfunction "35_35") (pintype "passive"))
      (node (ref "J2") (pin "36") (pinfunction "36_36") (pintype "passive"))
      (node (ref "J2") (pin "37") (pinfunction "37_37") (pintype "passive"))
      (node (ref "J2") (pin "38") (pinfunction "38_38") (pintype "passive"))
      (node (ref "Q5") (pin "5") (pinfunction "D_5") (pintype "passive"))
      (node (ref "Q5") (pin "6") (pinfunction "D_6") (pintype "passive"))
      (node (ref "Q5") (pin "7") (pinfunction "D_7") (pintype "passive"))
      (node (ref "Q5") (pin "8") (pinfunction "D_8") (pintype "passive"))
    )
    (net (code "40") (name "HEATER_PWR") (class "Default")
      (node (ref "C41") (pin "2") (pinfunction "2_2") (pintype "passive"))
      (node (ref "C62") (pin "2") (pinfunction "2_2") (pintype "passive"))
      (node (ref "C65") (pin "2") (pinfunction "2_2") (pintype "passive"))
      (node (ref "C81") (pin "2") (pinfunction "2_2") (pintype "passive"))
      (node (ref "C82") (pin "2") (pinfunction "2_2") (pintype "passive"))
      (node (ref "J2") (pin "10") (pinfunction "10_10") (pintype "passive"))
      (node (ref "J2") (pin "11") (pinfunction "11_11") (pintype "passive"))
      (node (ref "J2") (pin "12") (pinfunction "12_12") (pintype "passive"))
      (node (ref "J2") (pin "13") (pinfunction "13_13") (pintype "passive"))
      (node (ref "J2") (pin "14") (pinfunction "14_14") (pintype "passive"))
      (node (ref "J2") (pin "15") (pinfunction "15_15") (pintype "passive"))
      (node (ref "J2") (pin "16") (pinfunction "16_16") (pintype "passive"))
      (node (ref "J2") (pin "17") (pinfunction "17_17") (pintype "passive"))
      (node (ref "J2") (pin "18") (pinfunction "18_18") (pintype "passive"))
      (node (ref "J2") (pin "19") (pinfunction "19_19") (pintype "passive"))
      (node (ref "J2") (pin "20") (pinfunction "20_20") (pintype "passive"))
      (node (ref "J2") (pin "21") (pinfunction "21_21") (pintype "passive"))
      (node (ref "J2") (pin "22") (pinfunction "22_22") (pintype "passive"))
      (node (ref "J2") (pin "7") (pinfunction "7_7") (pintype "passive"))
      (node (ref "J2") (pin "8") (pinfunction "8_8") (pintype "passive"))
      (node (ref "J2") (pin "9") (pinfunction "9_9") (pintype "passive"))
      (node (ref "R71") (pin "2") (pinfunction "2_2") (pintype "passive"))
      (node (ref "U7") (pin "14") (pinfunction "VOUT_14") (pintype "power_in"))
      (node (ref "U7") (pin "15") (pinfunction "VOUT_15") (pintype "power_in"))
      (node (ref "U7") (pin "16") (pinfunction "VOUT_16") (pintype "power_in"))
    )
    (net (code "41") (name "MOTOR_CATHODE") (class "Default")
      (node (ref "J1") (pin "5") (pinfunction "5_5") (pintype "passive"))
      (node (ref "Q4") (pin "5") (pinfunction "D_5") (pintype "passive"))
      (node (ref "Q4") (pin "6") (pinfunction "D_6") (pintype "passive"))
      (node (ref "Q4") (pin "7") (pinfunction "D_7") (pintype "passive"))
      (node (ref "Q4") (pin "8") (pinfunction "D_8") (pintype "passive"))
    )
    (net (code "42") (name "Net-(C38-Pad2)") (class "Default")
      (node (ref "C38") (pin "2") (pinfunction "2_2") (pintype "passive"))
      (node (ref "R56") (pin "1") (pinfunction "1_1") (pintype "passive"))
    )
    (net (code "43") (name "Net-(C77-Pad1)") (class "Default")
      (node (ref "C77") (pin "1") (pinfunction "1_1") (pintype "passive"))
      (node (ref "R60") (pin "2") (pinfunction "2_2") (pintype "passive"))
    )
    (net (code "44") (name "Net-(U13-FB{slash}VSET)") (class "Default")
      (node (ref "R75") (pin "1") (pinfunction "1_1") (pintype "passive"))
      (node (ref "R76") (pin "2") (pinfunction "2_2") (pintype "passive"))
      (node (ref "U13") (pin "1") (pinfunction "FB/VSET_1") (pintype "input"))
    )
    (net (code "45") (name "Net-(U13-MODE{slash}S-CONF)") (class "Default")
      (node (ref "R74") (pin "1") (pinfunction "1_1") (pintype "passive"))
      (node (ref "R77") (pin "2") (pinfunction "2_2") (pintype "passive"))
      (node (ref "U13") (pin "8") (pinfunction "MODE/S-CONF_8") (pintype "input"))
    )
    (net (code "46") (name "VBAT") (class "Default")
      (node (ref "C32") (pin "2") (pinfunction "2_2") (pintype "passive"))
      (node (ref "C33") (pin "1") (pinfunction "1_1") (pintype "passive"))
      (node (ref "C34") (pin "1") (pinfunction "1_1") (pintype "passive"))
      (node (ref "C35") (pin "2") (pinfunction "2_2") (pintype "passive"))
      (node (ref "C69") (pin "2") (pinfunction "2_2") (pintype "passive"))
      (node (ref "C74") (pin "2") (pinfunction "2_2") (pintype "passive"))
      (node (ref "C83") (pin "2") (pinfunction "2_2") (pintype "passive"))
      (node (ref "C85") (pin "2") (pinfunction "2_2") (pintype "passive"))
      (node (ref "L2") (pin "1") (pinfunction "1_1") (pintype "passive"))
      (node (ref "L4") (pin "1") (pinfunction "1_1") (pintype "passive"))
      (node (ref "R74") (pin "2") (pinfunction "2_2") (pintype "passive"))
      (node (ref "U13") (pin "6") (pinfunction "VIN_6") (pintype "power_in"))
      (node (ref "U13") (pin "7") (pinfunction "EN_7") (pintype "input"))
      (node (ref "U16") (pin "3") (pinfunction "BIAS_3") (pintype "power_in"))
      (node (ref "U7") (pin "9") (pinfunction "VIN_9") (pintype "passive"))
    )
    (net (code "47") (name "VCC_MOTOR") (class "Default")
      (node (ref "C39") (pin "1") (pinfunction "1_1") (pintype "passive"))
      (node (ref "C40") (pin "2") (pinfunction "2_2") (pintype "passive"))
      (node (ref "C70") (pin "2") (pinfunction "2_2") (pintype "passive"))
      (node (ref "C71") (pin "2") (pinfunction "2_2") (pintype "passive"))
      (node (ref "C72") (pin "2") (pinfunction "2_2") (pintype "passive"))
      (node (ref "C78") (pin "1") (pinfunction "1_1") (pintype "passive"))
      (node (ref "C79") (pin "1") (pinfunction "1_1") (pintype "passive"))
      (node (ref "D1") (pin "K") (pinfunction "K_K") (pintype "passive"))
      (node (ref "D7") (pin "K") (pinfunction "K_K") (pintype "passive"))
      (node (ref "J1") (pin "6") (pinfunction "6_6") (pintype "passive"))
      (node (ref "R32") (pin "2") (pinfunction "2_2") (pintype "passive"))
      (node (ref "TP21") (pin "1") (pinfunction "1_1") (pintype "passive"))
    )
    (net (code "48") (name "unconnected-(U13-PG-Pad2)") (class "Default")
      (node (ref "U13") (pin "2") (pinfunction "PG_2") (pintype "output"))
    )
  )
)
